# schematic.net
KiCad netlist of a schematic drawn in EasyEDA
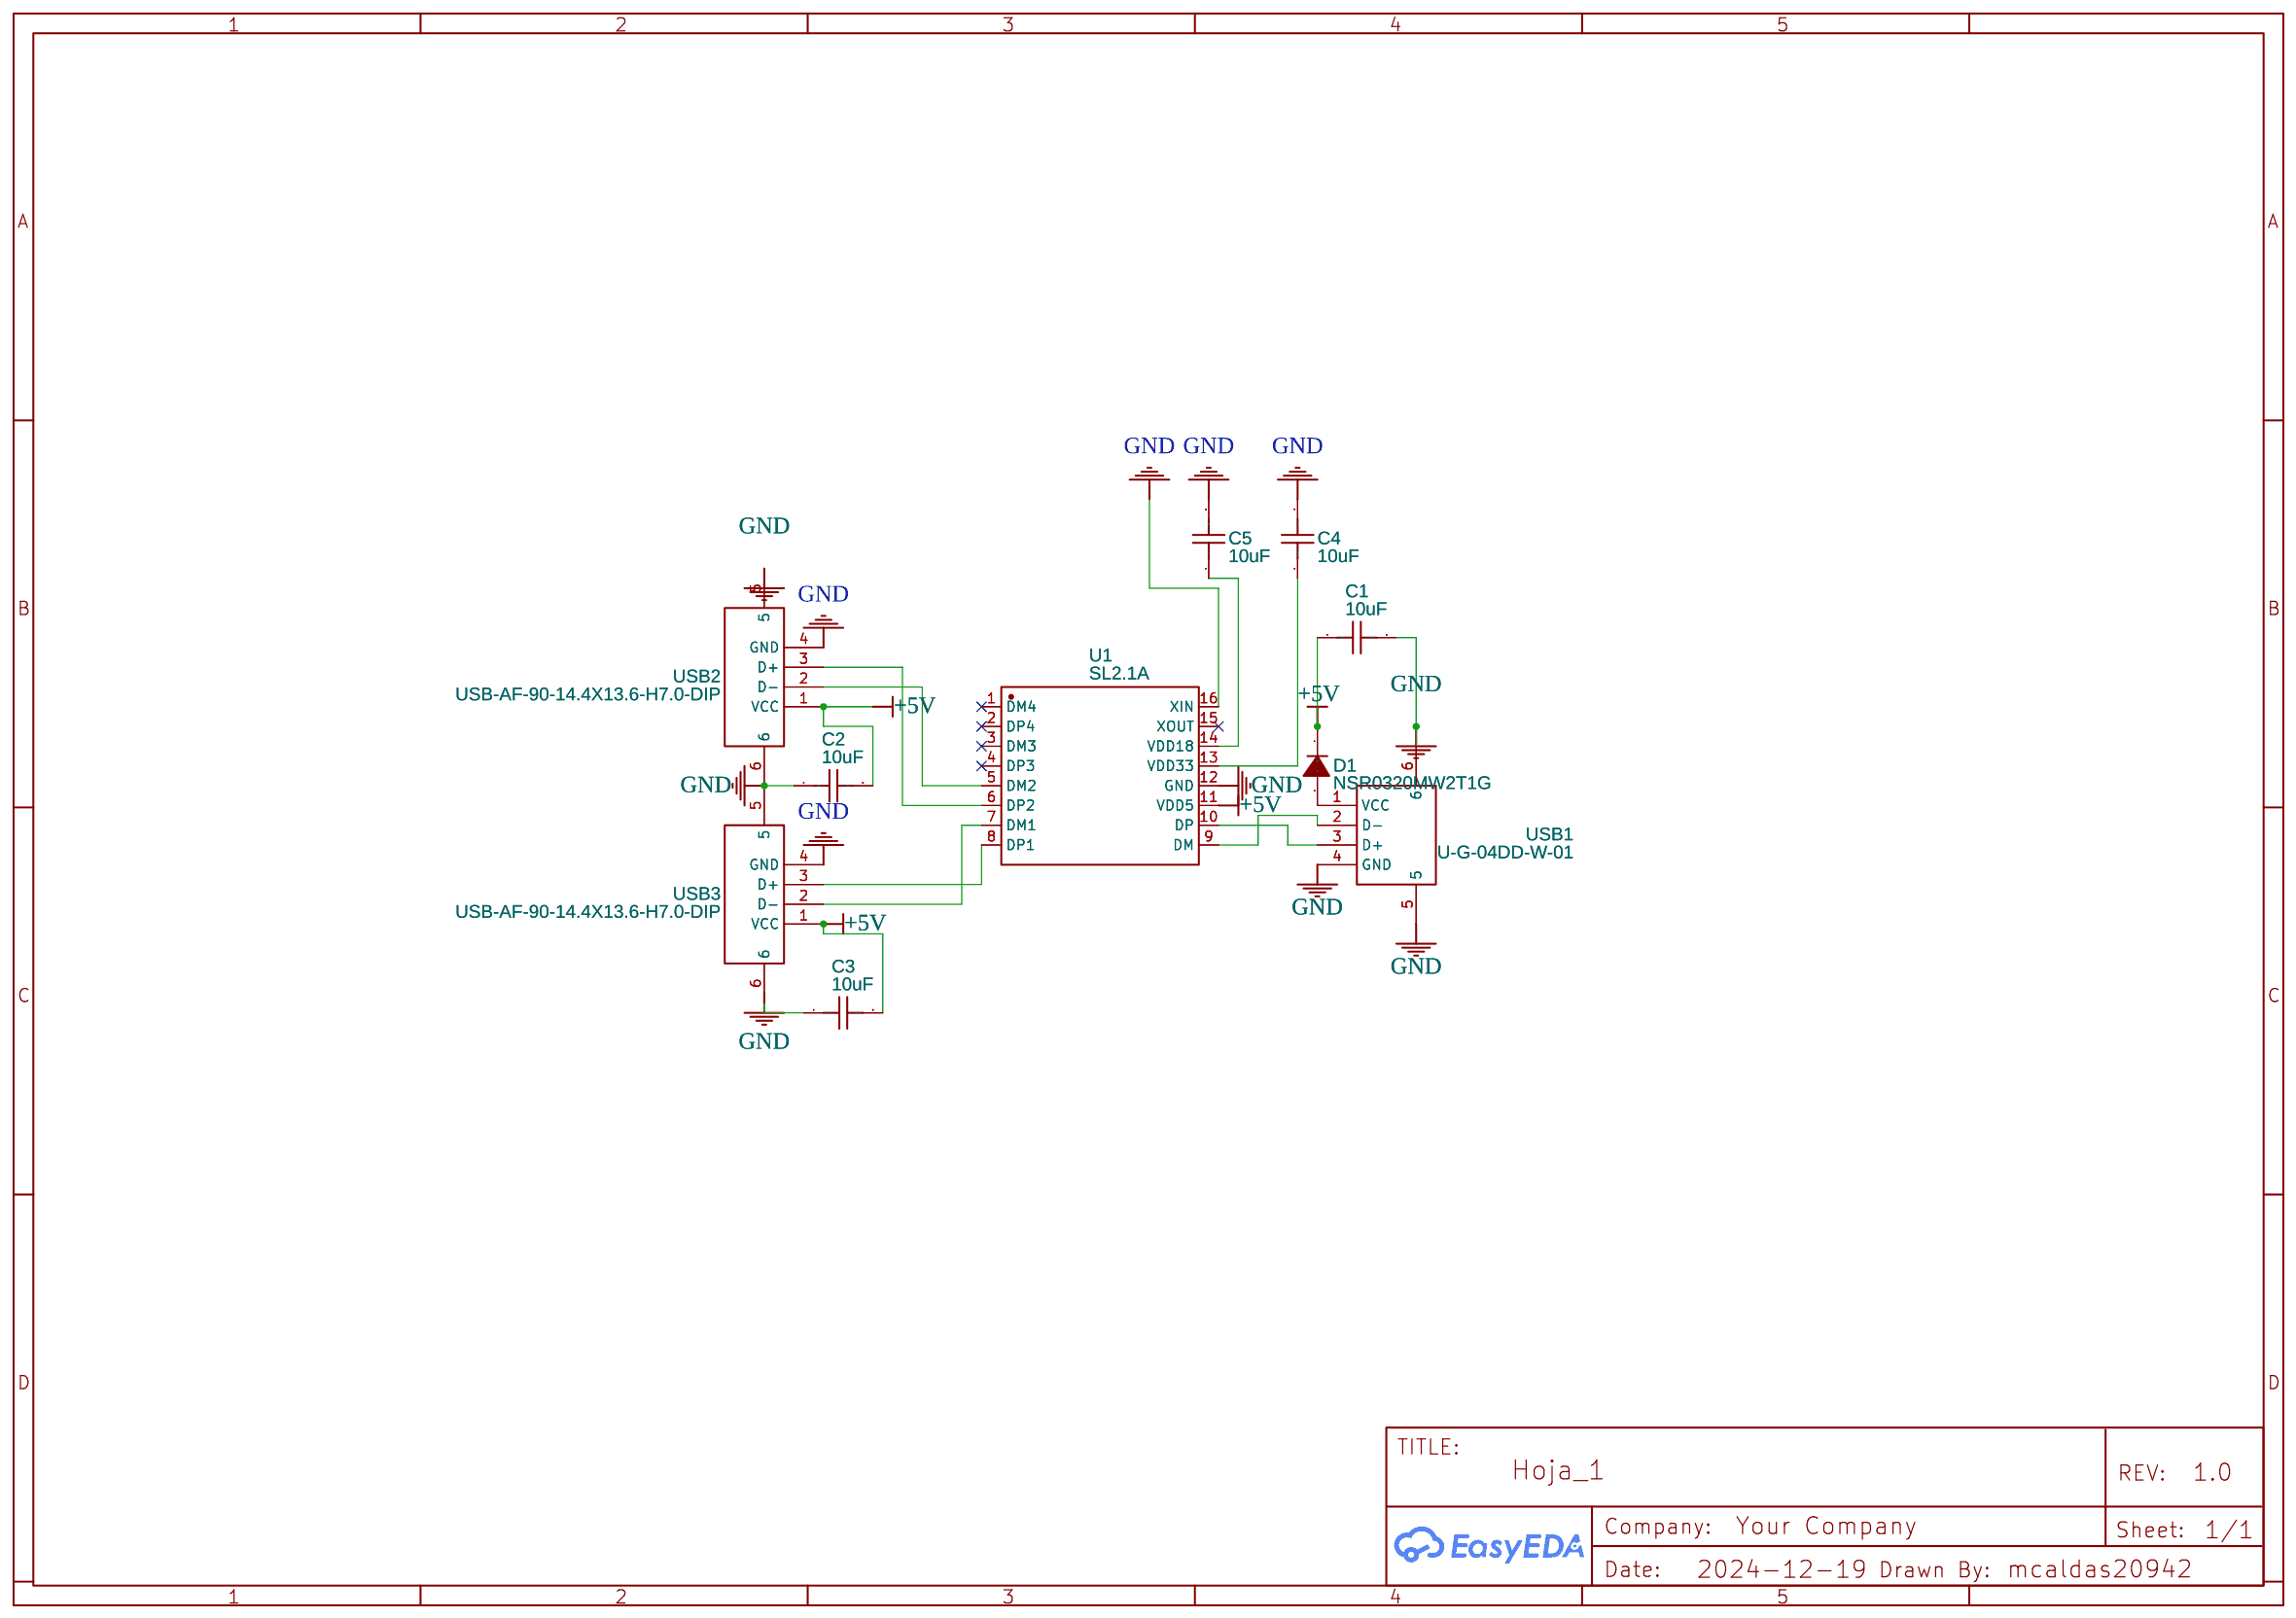
[diagram p0: schematic sheet]

(export (version "E")
  (design (tool "Eeschema 10.0.6"))
  (components
    (comp (ref "C1")
      (value "10uF")
      (fields
        (field (name "Manufacturer Part") "CL10A106KP8NNNC")
        (field (name "Manufacturer") "SAMSUNG(三星)")
      )
      (libsource (lib "") (part "CL10A106KP8NNNC"))
    )
    (comp (ref "C2")
      (value "10uF")
      (fields
        (field (name "Manufacturer Part") "CL10A106KP8NNNC")
        (field (name "Manufacturer") "SAMSUNG(三星)")
      )
      (libsource (lib "") (part "CL10A106KP8NNNC"))
    )
    (comp (ref "C3")
      (value "10uF")
      (fields
        (field (name "Manufacturer Part") "CL10A106KP8NNNC")
        (field (name "Manufacturer") "SAMSUNG(三星)")
      )
      (libsource (lib "") (part "CL10A106KP8NNNC"))
    )
    (comp (ref "C4")
      (value "10uF")
      (fields
        (field (name "Manufacturer Part") "CL10A106KP8NNNC")
        (field (name "Manufacturer") "SAMSUNG(三星)")
      )
      (libsource (lib "") (part "CL10A106KP8NNNC_1"))
    )
    (comp (ref "C5")
      (value "10uF")
      (fields
        (field (name "Manufacturer Part") "CL10A106KP8NNNC")
        (field (name "Manufacturer") "SAMSUNG(三星)")
      )
      (libsource (lib "") (part "CL10A106KP8NNNC_2"))
    )
    (comp (ref "D1")
      (value "NSR0320MW2T1G")
      (fields (field (name "Manufacturer") "onsemi(安森美)"))
      (libsource (lib "") (part "NSR0320MW2T1G"))
    )
    (comp (ref "U1")
      (value "SL2.1A")
      (fields (field (name "Manufacturer") "CoreChips(和芯润德)"))
      (libsource (lib "") (part "SL2.1A"))
    )
    (comp (ref "USB1")
      (value "U-G-04DD-W-01")
      (fields (field (name "Manufacturer Part") "U-G-O4DD-W-1") (field (name "Manufacturer") "韩国韩荣"))
      (libsource (lib "") (part "U-G-04DD-W-01"))
    )
    (comp (ref "USB2")
      (value "USB-AF-90-14.4X13.6-H7.0-DIP")
      (fields (field (name "Manufacturer Part") "903-131A1011D10100") (field (name "Manufacturer") "精拓金"))
      (libsource (lib "") (part "USB-AF-90-14.4X13.6-H7.0-DIP"))
    )
    (comp (ref "USB3")
      (value "USB-AF-90-14.4X13.6-H7.0-DIP")
      (fields (field (name "Manufacturer Part") "903-131A1011D10100") (field (name "Manufacturer") "精拓金"))
      (libsource (lib "") (part "USB-AF-90-14.4X13.6-H7.0-DIP"))
    )
  )
  (nets
    (net (code "1") (name "+5V") (class "Default")
      (node (ref "C1") (pin "1") (pinfunction "1_1") (pintype "unspecified"))
      (node (ref "C2") (pin "2") (pinfunction "2_2") (pintype "unspecified"))
      (node (ref "C3") (pin "2") (pinfunction "2_2") (pintype "unspecified"))
      (node (ref "D1") (pin "1") (pinfunction "C_1") (pintype "unspecified"))
      (node (ref "U1") (pin "11") (pinfunction "VDD5_11") (pintype "unspecified"))
      (node (ref "USB2") (pin "1") (pinfunction "VCC_1") (pintype "unspecified"))
      (node (ref "USB3") (pin "1") (pinfunction "VCC_1") (pintype "unspecified"))
    )
    (net (code "2") (name "GND") (class "Default")
      (node (ref "C1") (pin "2") (pinfunction "2_2") (pintype "unspecified"))
      (node (ref "C2") (pin "1") (pinfunction "1_1") (pintype "unspecified"))
      (node (ref "C4") (pin "1") (pinfunction "1_1") (pintype "unspecified"))
      (node (ref "C5") (pin "2") (pinfunction "2_2") (pintype "unspecified"))
      (node (ref "U1") (pin "12") (pinfunction "GND_12") (pintype "unspecified"))
      (node (ref "U1") (pin "16") (pinfunction "XIN_16") (pintype "unspecified"))
      (node (ref "USB1") (pin "4") (pinfunction "GND_4") (pintype "unspecified"))
      (node (ref "USB1") (pin "5") (pinfunction "5_5") (pintype "unspecified"))
      (node (ref "USB1") (pin "6") (pinfunction "6_6") (pintype "unspecified"))
      (node (ref "USB2") (pin "4") (pinfunction "GND_4") (pintype "unspecified"))
      (node (ref "USB2") (pin "5") (pinfunction "5_5") (pintype "unspecified"))
      (node (ref "USB2") (pin "6") (pinfunction "6_6") (pintype "unspecified"))
      (node (ref "USB3") (pin "4") (pinfunction "GND_4") (pintype "unspecified"))
      (node (ref "USB3") (pin "5") (pinfunction "5_5") (pintype "unspecified"))
    )
    (net (code "3") (name "Net-(C3-Pad1)") (class "Default")
      (node (ref "C3") (pin "1") (pinfunction "1_1") (pintype "unspecified"))
      (node (ref "USB3") (pin "6") (pinfunction "6_6") (pintype "unspecified"))
    )
    (net (code "4") (name "Net-(D1-A)") (class "Default")
      (node (ref "D1") (pin "2") (pinfunction "A_2") (pintype "unspecified"))
      (node (ref "USB1") (pin "1") (pinfunction "VCC_1") (pintype "unspecified"))
    )
    (net (code "5") (name "Net-(U1-DM)") (class "Default")
      (node (ref "U1") (pin "9") (pinfunction "DM_9") (pintype "unspecified"))
      (node (ref "USB1") (pin "2") (pinfunction "D-_2") (pintype "unspecified"))
    )
    (net (code "6") (name "Net-(U1-DM1)") (class "Default")
      (node (ref "U1") (pin "7") (pinfunction "DM1_7") (pintype "unspecified"))
      (node (ref "USB3") (pin "2") (pinfunction "D-_2") (pintype "unspecified"))
    )
    (net (code "7") (name "Net-(U1-DM2)") (class "Default")
      (node (ref "U1") (pin "5") (pinfunction "DM2_5") (pintype "unspecified"))
      (node (ref "USB2") (pin "2") (pinfunction "D-_2") (pintype "unspecified"))
    )
    (net (code "8") (name "Net-(U1-DP)") (class "Default")
      (node (ref "U1") (pin "10") (pinfunction "DP_10") (pintype "unspecified"))
      (node (ref "USB1") (pin "3") (pinfunction "D+_3") (pintype "unspecified"))
    )
    (net (code "9") (name "Net-(U1-DP1)") (class "Default")
      (node (ref "U1") (pin "8") (pinfunction "DP1_8") (pintype "unspecified"))
      (node (ref "USB3") (pin "3") (pinfunction "D+_3") (pintype "unspecified"))
    )
    (net (code "10") (name "Net-(U1-DP2)") (class "Default")
      (node (ref "U1") (pin "6") (pinfunction "DP2_6") (pintype "unspecified"))
      (node (ref "USB2") (pin "3") (pinfunction "D+_3") (pintype "unspecified"))
    )
    (net (code "11") (name "Net-(U1-VDD18)") (class "Default")
      (node (ref "C5") (pin "1") (pinfunction "1_1") (pintype "unspecified"))
      (node (ref "U1") (pin "14") (pinfunction "VDD18_14") (pintype "unspecified"))
    )
    (net (code "12") (name "Net-(U1-VDD33)") (class "Default")
      (node (ref "C4") (pin "2") (pinfunction "2_2") (pintype "unspecified"))
      (node (ref "U1") (pin "13") (pinfunction "VDD33_13") (pintype "unspecified"))
    )
    (net (code "13") (name "unconnected-(U1-DM3-Pad3)") (class "Default")
      (node (ref "U1") (pin "3") (pinfunction "DM3_3") (pintype "unspecified+no_connect"))
    )
    (net (code "14") (name "unconnected-(U1-DM4-Pad1)") (class "Default")
      (node (ref "U1") (pin "1") (pinfunction "DM4_1") (pintype "unspecified+no_connect"))
    )
    (net (code "15") (name "unconnected-(U1-DP3-Pad4)") (class "Default")
      (node (ref "U1") (pin "4") (pinfunction "DP3_4") (pintype "unspecified+no_connect"))
    )
    (net (code "16") (name "unconnected-(U1-DP4-Pad2)") (class "Default")
      (node (ref "U1") (pin "2") (pinfunction "DP4_2") (pintype "unspecified+no_connect"))
    )
    (net (code "17") (name "unconnected-(U1-XOUT-Pad15)") (class "Default")
      (node (ref "U1") (pin "15") (pinfunction "XOUT_15") (pintype "unspecified+no_connect"))
    )
  )
)
